# RTU_LMG_RTC_Linear_Voltage_Regulator_3V3.net
KiCad netlist of a schematic drawn in Altium Designer
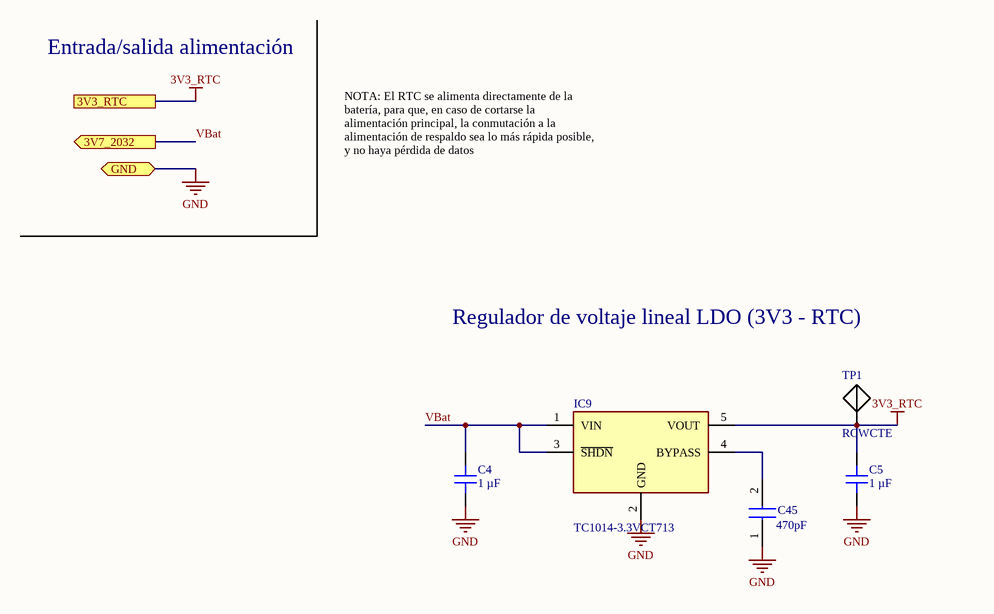
[diagram p0: RTU_LMG_RTC_Linear_Voltage_Regulator_3V3.SchDoc]

(export (version "E")
  (design (tool "Eeschema 10.0.6"))
  (components
    (comp (ref "C4")
      (value "1 µF")
      (footprint "CAP 0402_1005")
      (description "CAP CER 1UF 16V X5R 0402")
      (fields
        (field (name "PART NUMBER") "CL05A105KO5NNNC")
        (field (name "MANUFACTURER") "Samsung Electro-Mechanics")
      )
      (libsource (lib "Celestial Altium Library - altium_library") (part "Capacitor"))
    )
    (comp (ref "C5")
      (value "1 µF")
      (footprint "CAP 0402_1005")
      (description "CAP CER 1UF 16V X5R 0402")
      (fields
        (field (name "PART NUMBER") "CL05A105KO5NNNC")
        (field (name "MANUFACTURER") "Samsung Electro-Mechanics")
      )
      (libsource (lib "Celestial Altium Library - altium_library") (part "Capacitor"))
    )
    (comp (ref "C45")
      (value "470pF")
      (footprint "DIN_DC_Base_Board_components_PCB_footprints:CAPACITOR_SMD_0402")
      (description "Capacitor")
      (fields
        (field (name "MANUFACTURER_PART_NUMBER") "GRM155R71H471KA01D")
        (field (name "MOUSER PART NUMBER") "81-GRM36X471K50")
      )
      (libsource (lib "DIN_DC_Base_Board_components_SCH_footprints") (part "GRM155R71H471KA01D"))
    )
    (comp (ref "IC9")
      (value "TC1014-3.3VCT713")
      (footprint "DIN_DC_Base_Board_components_PCB_footprints:SOT-23-5")
      (description "Fuente regulada LDO - 3V3 - 50mA")
      (fields (field (name "MOUSER PART NUMBER") "579-TC1014-3.3VCT713"))
      (libsource (lib "DIN_DC_Base_Board_components_SCH_footprints") (part "TC1014-3.3VCT713"))
    )
    (comp (ref "TP1")
      (value "RCWCTE")
      (footprint "RCWCTE")
      (description "- PC Test Point - - Plating Surface Mount Mounting Type")
      (fields (field (name "MF") "KOA Speer") (field (name "DIGI-KEY_PART_NUMBER") "2019-RCWCTETR-ND"))
      (libsource (lib "DIN_DC_Base_Board_components_SCH_footprints") (part "RCWCTE"))
    )
  )
  (nets
    (net (code "1") (name "/VBat") (class "Default")
      (node (ref "C4") (pin "1") (pinfunction "1_1") (pintype "passive"))
      (node (ref "IC9") (pin "1") (pinfunction "VIN_1") (pintype "passive"))
      (node (ref "IC9") (pin "3") (pinfunction "~{SHDN}_3") (pintype "passive"))
    )
    (net (code "2") (name "3V3_RTC") (class "Default")
      (node (ref "C5") (pin "1") (pinfunction "1_1") (pintype "passive"))
      (node (ref "IC9") (pin "5") (pinfunction "VOUT_5") (pintype "passive"))
      (node (ref "TP1") (pin "1") (pinfunction "TP_1") (pintype "passive"))
    )
    (net (code "3") (name "GND") (class "Default")
      (node (ref "C4") (pin "2") (pinfunction "2_2") (pintype "passive"))
      (node (ref "C45") (pin "1") (pinfunction "1_1") (pintype "passive"))
      (node (ref "C5") (pin "2") (pinfunction "2_2") (pintype "passive"))
      (node (ref "IC9") (pin "2") (pinfunction "GND_2") (pintype "passive"))
    )
    (net (code "4") (name "Net-(IC9-BYPASS)") (class "Default")
      (node (ref "C45") (pin "2") (pinfunction "2_2") (pintype "passive"))
      (node (ref "IC9") (pin "4") (pinfunction "BYPASS_4") (pintype "passive"))
    )
  )
)
